# eeZeeTiny841.net
KiCad netlist of a schematic drawn in EAGLE
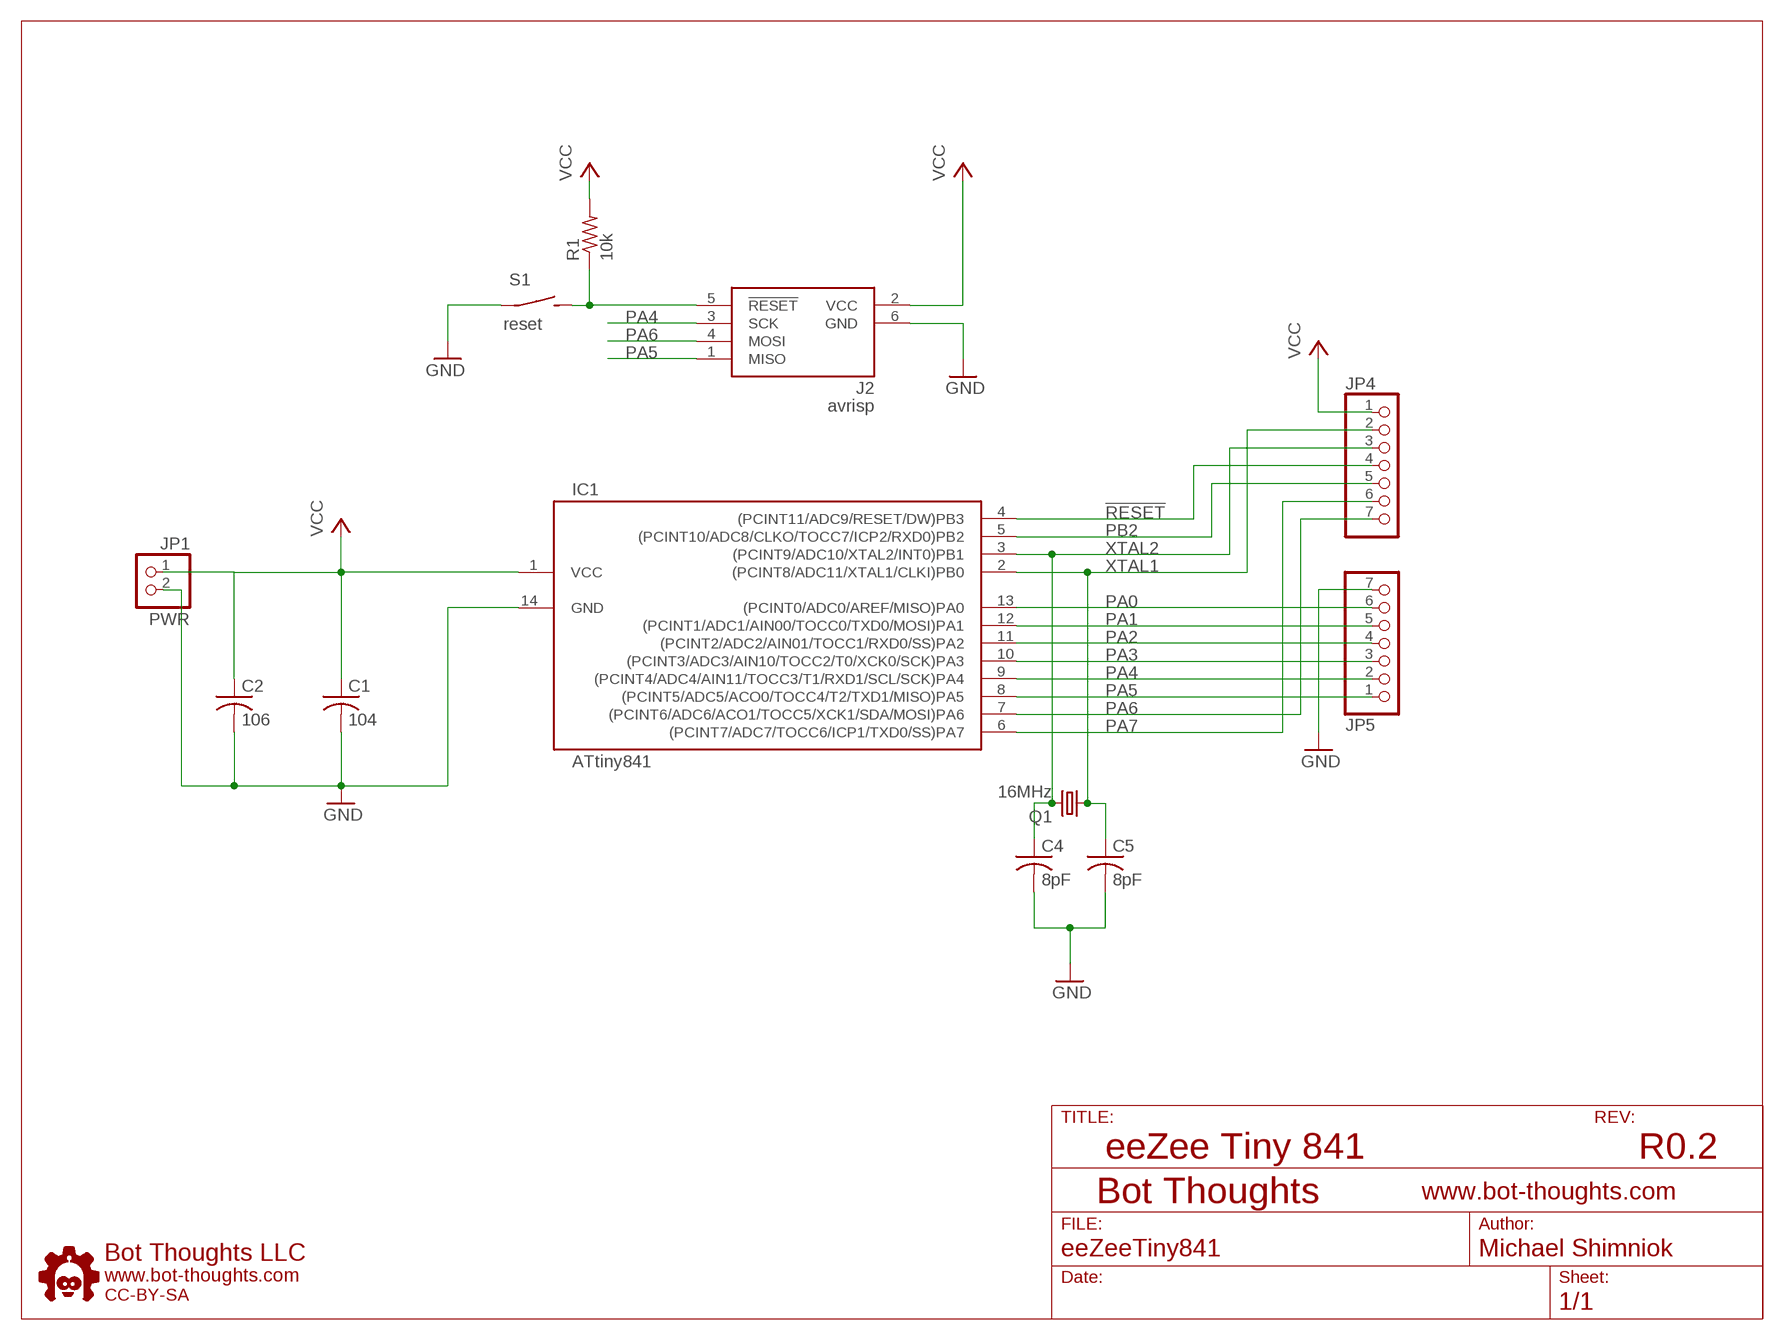
[diagram p0: schematic, sheet 1]

(export (version "E")
  (design (tool "Eeschema 10.0.6"))
  (components
    (comp (ref "C1")
      (value "104")
      (footprint "eagle-import:C0603")
      (fields (field (name "PARTNO") "0603YC104KAT2A"))
      (libsource (lib "eagle-import") (part "C-USC0603"))
    )
    (comp (ref "C2")
      (value "106")
      (footprint "eagle-import:C1206")
      (fields (field (name "PARTNO") "MCTT21X106M6R3CT"))
      (libsource (lib "eagle-import") (part "C-USC1206"))
    )
    (comp (ref "C4")
      (value "8pF")
      (footprint "eagle-import:C0603")
      (fields (field (name "PARTNO") "0603YC104KAT2A"))
      (libsource (lib "eagle-import") (part "C-USC0603"))
    )
    (comp (ref "C5")
      (value "8pF")
      (footprint "eagle-import:C0603")
      (fields (field (name "PARTNO") "0603YC104KAT2A"))
      (libsource (lib "eagle-import") (part "C-USC0603"))
    )
    (comp (ref "IC1")
      (value "ATtiny841")
      (footprint "eagle-import:14SOICN")
      (libsource (lib "eagle-import") (part "ATTINY441/841-SSU"))
    )
    (comp (ref "J2")
      (value "avrisp")
      (footprint "eagle-import:CON6P2R")
      (libsource (lib "eagle-import") (part "AVRISP6_COMPACT"))
    )
    (comp (ref "JP1")
      (value "PWR")
      (footprint "eagle-import:1X02-S")
      (libsource (lib "eagle-import") (part "PINHD-1X02_2.54-S"))
    )
    (comp (ref "JP4")
      (value "PINHD-1X07_2.54-S")
      (footprint "eagle-import:1X07-S")
      (libsource (lib "eagle-import") (part "PINHD-1X07_2.54-S"))
    )
    (comp (ref "JP5")
      (value "PINHD-1X07_2.54-S")
      (footprint "eagle-import:1X07-S")
      (libsource (lib "eagle-import") (part "PINHD-1X07_2.54-S"))
    )
    (comp (ref "Q1")
      (value "16MHz")
      (footprint "eagle-import:NDK_2PAD_5X3")
      (libsource (lib "eagle-import") (part "CRYSTALNDK5X3"))
    )
    (comp (ref "R1")
      (value "10k")
      (footprint "eagle-import:R0603")
      (fields (field (name "PARTNO") "ERJ-3GEYJ103V"))
      (libsource (lib "eagle-import") (part "R-US_R0603"))
    )
    (comp (ref "S1")
      (value "reset")
      (footprint "eagle-import:6MMTACTILE_RECT")
      (libsource (lib "eagle-import") (part "SPST_TAC_RECT1"))
    )
    (comp (ref "U$1")
      (value "BTLOGO-LOGO-MD")
      (footprint "eagle-import:BTLOGOM")
      (libsource (lib "eagle-import") (part "BTLOGO-LOGO-MD"))
    )
  )
  (nets
    (net (code "1") (name "/PA0") (class "Default")
      (node (ref "IC1") (pin "13") (pinfunction "(PCINT0/ADC0/AREF/MISO)PA0_13") (pintype "bidirectional"))
      (node (ref "JP5") (pin "6") (pinfunction "6_6") (pintype "passive"))
    )
    (net (code "2") (name "/PA1") (class "Default")
      (node (ref "IC1") (pin "12") (pinfunction "(PCINT1/ADC1/AIN00/TOCC0/TXD0/MOSI)PA1_12") (pintype "bidirectional"))
      (node (ref "JP5") (pin "5") (pinfunction "5_5") (pintype "passive"))
    )
    (net (code "3") (name "/PA2") (class "Default")
      (node (ref "IC1") (pin "11") (pinfunction "(PCINT2/ADC2/AIN01/TOCC1/RXD0/SS)PA2_11") (pintype "bidirectional"))
      (node (ref "JP5") (pin "4") (pinfunction "4_4") (pintype "passive"))
    )
    (net (code "4") (name "/PA3") (class "Default")
      (node (ref "IC1") (pin "10") (pinfunction "(PCINT3/ADC3/AIN10/TOCC2/T0/XCK0/SCK)PA3_10") (pintype "bidirectional"))
      (node (ref "JP5") (pin "3") (pinfunction "3_3") (pintype "passive"))
    )
    (net (code "5") (name "/PA4") (class "Default")
      (node (ref "IC1") (pin "9") (pinfunction "(PCINT4/ADC4/AIN11/TOCC3/T1/RXD1/SCL/SCK)PA4_9") (pintype "bidirectional"))
      (node (ref "J2") (pin "3") (pinfunction "SCK_3") (pintype "output"))
      (node (ref "JP5") (pin "2") (pinfunction "2_2") (pintype "passive"))
    )
    (net (code "6") (name "/PA5") (class "Default")
      (node (ref "IC1") (pin "8") (pinfunction "(PCINT5/ADC5/ACO0/TOCC4/T2/TXD1/MISO)PA5_8") (pintype "bidirectional"))
      (node (ref "J2") (pin "1") (pinfunction "MISO_1") (pintype "input"))
      (node (ref "JP5") (pin "1") (pinfunction "1_1") (pintype "passive"))
    )
    (net (code "7") (name "/PA6") (class "Default")
      (node (ref "IC1") (pin "7") (pinfunction "(PCINT6/ADC6/ACO1/TOCC5/XCK1/SDA/MOSI)PA6_7") (pintype "bidirectional"))
      (node (ref "J2") (pin "4") (pinfunction "MOSI_4") (pintype "output"))
      (node (ref "JP4") (pin "7") (pinfunction "7_7") (pintype "passive"))
    )
    (net (code "8") (name "/PA7") (class "Default")
      (node (ref "IC1") (pin "6") (pinfunction "(PCINT7/ADC7/TOCC6/ICP1/TXD0/SS)PA7_6") (pintype "bidirectional"))
      (node (ref "JP4") (pin "6") (pinfunction "6_6") (pintype "passive"))
    )
    (net (code "9") (name "/PB2") (class "Default")
      (node (ref "IC1") (pin "5") (pinfunction "(PCINT10/ADC8/CLKO/TOCC7/ICP2/RXD0)PB2_5") (pintype "bidirectional"))
      (node (ref "JP4") (pin "5") (pinfunction "5_5") (pintype "passive"))
    )
    (net (code "10") (name "/XTAL1") (class "Default")
      (node (ref "C5") (pin "1") (pinfunction "1_1") (pintype "passive"))
      (node (ref "IC1") (pin "2") (pinfunction "(PCINT8/ADC11/XTAL1/CLKI)PB0_2") (pintype "bidirectional"))
      (node (ref "JP4") (pin "2") (pinfunction "2_2") (pintype "passive"))
      (node (ref "Q1") (pin "P$1") (pinfunction "1_P$1") (pintype "passive"))
    )
    (net (code "11") (name "/XTAL2") (class "Default")
      (node (ref "C4") (pin "1") (pinfunction "1_1") (pintype "passive"))
      (node (ref "IC1") (pin "3") (pinfunction "(PCINT9/ADC10/XTAL2/INT0)PB1_3") (pintype "bidirectional"))
      (node (ref "JP4") (pin "3") (pinfunction "3_3") (pintype "passive"))
      (node (ref "Q1") (pin "P$2") (pinfunction "2_P$2") (pintype "passive"))
    )
    (net (code "12") (name "/~{RESET}") (class "Default")
      (node (ref "IC1") (pin "4") (pinfunction "(PCINT11/ADC9/RESET/DW)PB3_4") (pintype "bidirectional"))
      (node (ref "J2") (pin "5") (pinfunction "~{RESET}_5") (pintype "output"))
      (node (ref "JP4") (pin "4") (pinfunction "4_4") (pintype "passive"))
      (node (ref "R1") (pin "1") (pinfunction "1_1") (pintype "passive"))
      (node (ref "S1") (pin "P$2") (pinfunction "S_P$2") (pintype "passive"))
    )
    (net (code "13") (name "GND") (class "Default")
      (node (ref "C1") (pin "2") (pinfunction "2_2") (pintype "passive"))
      (node (ref "C2") (pin "2") (pinfunction "2_2") (pintype "passive"))
      (node (ref "C4") (pin "2") (pinfunction "2_2") (pintype "passive"))
      (node (ref "C5") (pin "2") (pinfunction "2_2") (pintype "passive"))
      (node (ref "IC1") (pin "14") (pinfunction "GND_14") (pintype "bidirectional"))
      (node (ref "J2") (pin "6") (pinfunction "GND_6") (pintype "power_in"))
      (node (ref "JP1") (pin "2") (pinfunction "2_2") (pintype "passive"))
      (node (ref "JP5") (pin "7") (pinfunction "7_7") (pintype "passive"))
      (node (ref "S1") (pin "P$1") (pinfunction "P_P$1") (pintype "passive"))
    )
    (net (code "14") (name "VCC") (class "Default")
      (node (ref "C1") (pin "1") (pinfunction "1_1") (pintype "passive"))
      (node (ref "C2") (pin "1") (pinfunction "1_1") (pintype "passive"))
      (node (ref "IC1") (pin "1") (pinfunction "VCC_1") (pintype "bidirectional"))
      (node (ref "J2") (pin "2") (pinfunction "VCC_2") (pintype "power_in"))
      (node (ref "JP1") (pin "1") (pinfunction "1_1") (pintype "passive"))
      (node (ref "JP4") (pin "1") (pinfunction "1_1") (pintype "passive"))
      (node (ref "R1") (pin "2") (pinfunction "2_2") (pintype "passive"))
    )
  )
)
